# ESP-32-UNICLOCK-Z560M-V2.net
KiCad netlist of a schematic drawn in EAGLE
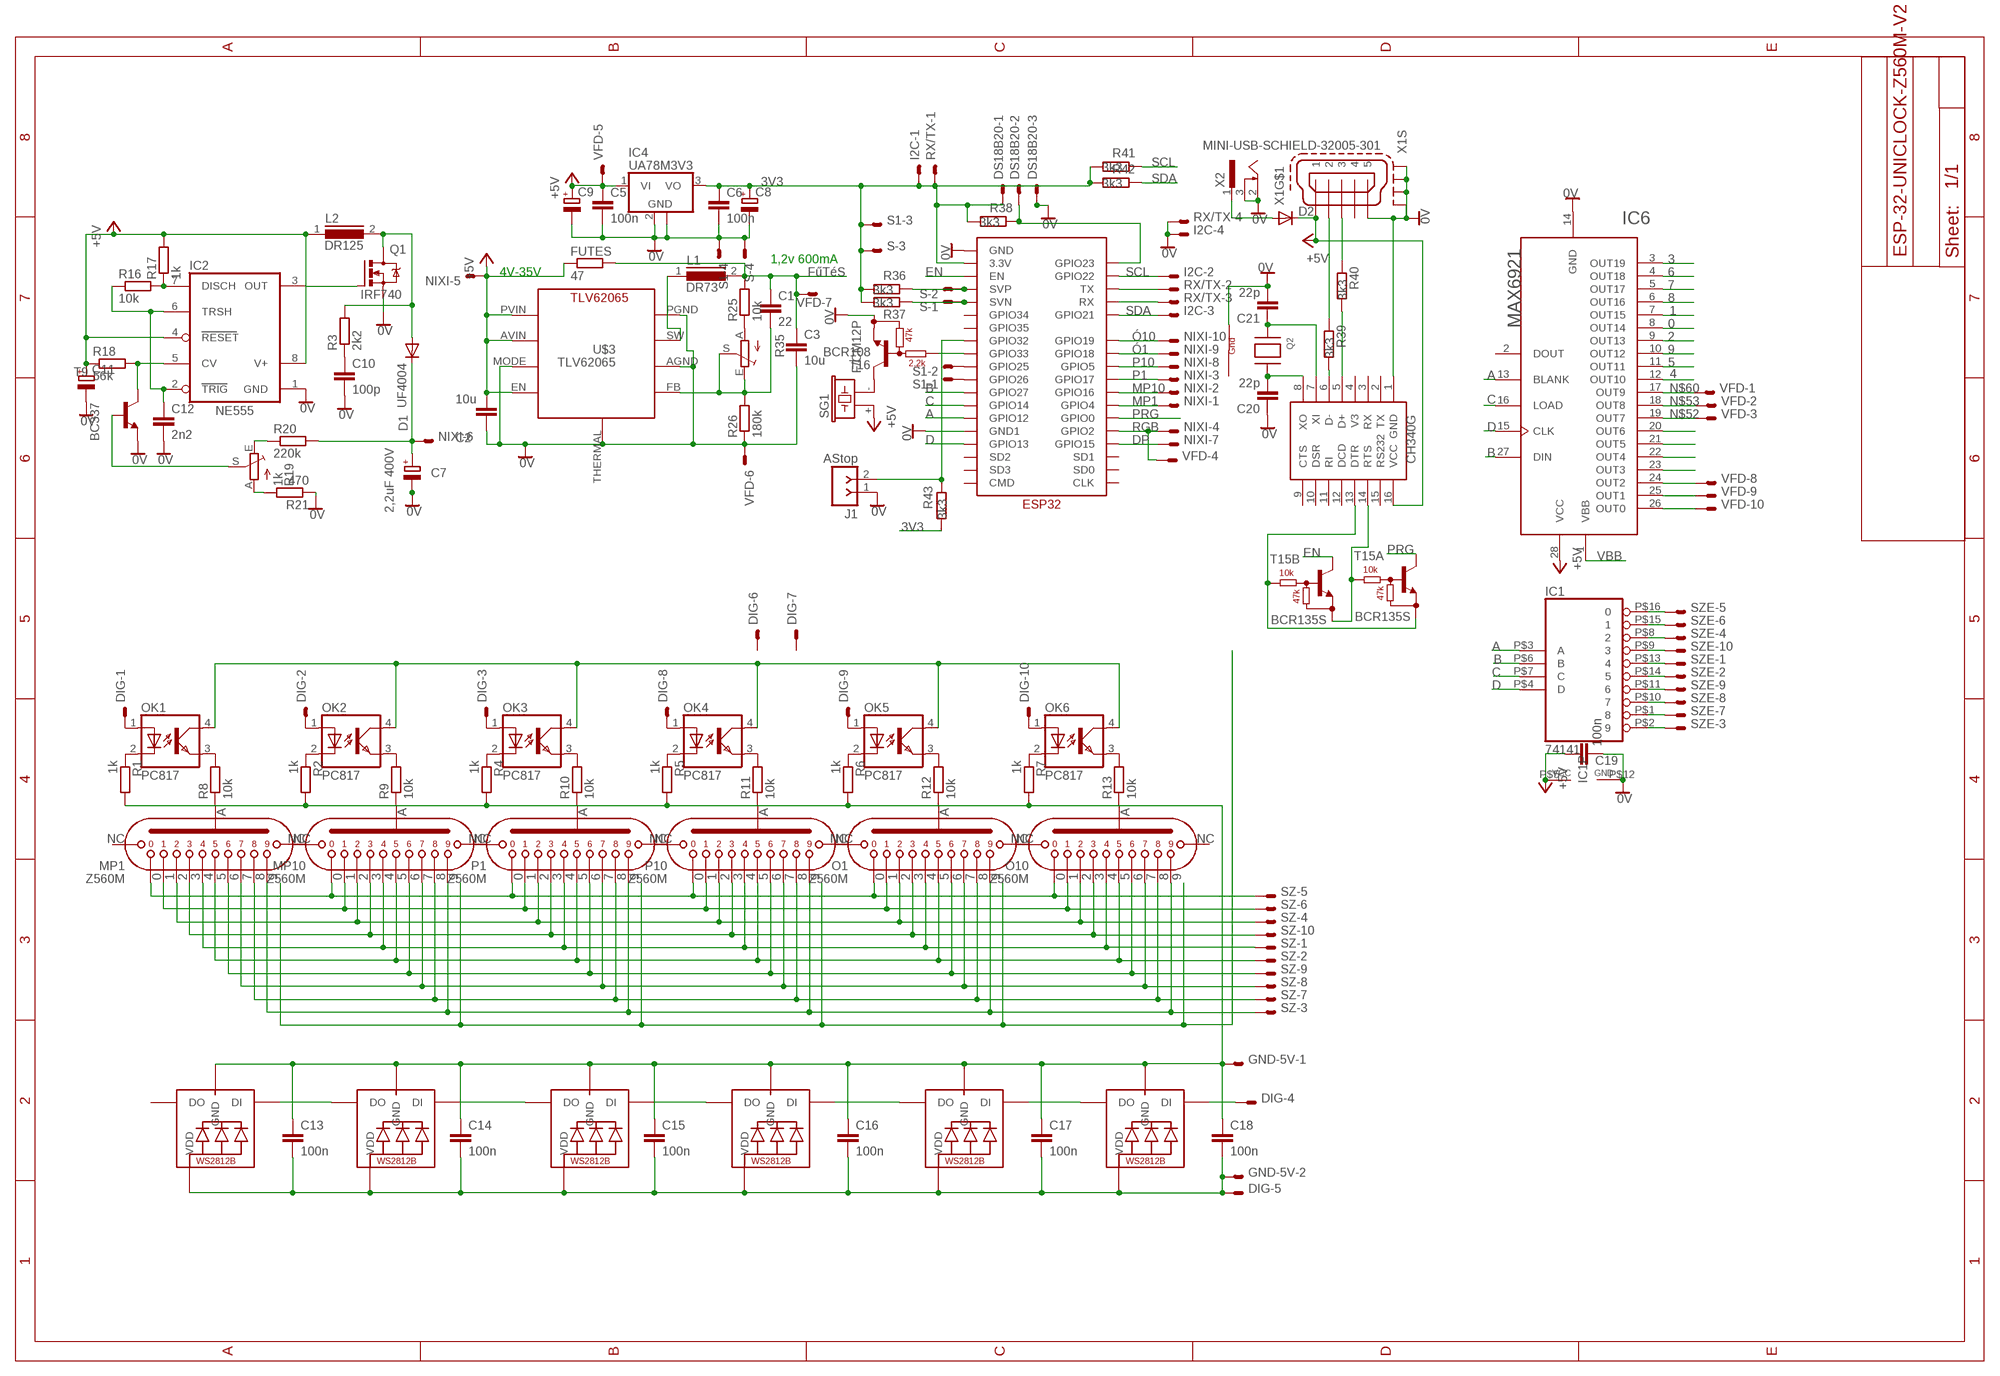
[diagram p0: schematic, sheet 1]

(export (version "E")
  (design (tool "Eeschema 10.0.6"))
  (components
    (comp (ref "C1")
      (value "22")
      (footprint "eagle-import:0603")
      (libsource (lib "eagle-import") (part "C0603"))
    )
    (comp (ref "C2")
      (value "10u")
      (footprint "eagle-import:1206")
      (libsource (lib "eagle-import") (part "C1206"))
    )
    (comp (ref "C3")
      (value "10u")
      (footprint "eagle-import:1206")
      (libsource (lib "eagle-import") (part "C1206"))
    )
    (comp (ref "C5")
      (value "100n")
      (footprint "eagle-import:0603")
      (libsource (lib "eagle-import") (part "C0603"))
    )
    (comp (ref "C6")
      (value "100n")
      (footprint "eagle-import:0603")
      (libsource (lib "eagle-import") (part "C0603"))
    )
    (comp (ref "C7")
      (value "2,2uF 400V")
      (footprint "eagle-import:E2,5-7")
      (libsource (lib "eagle-import") (part "CPOL-EUE2.5-7"))
    )
    (comp (ref "C8")
      (value "CPOL-EUE2.5-5")
      (footprint "eagle-import:E2,5-5")
      (libsource (lib "eagle-import") (part "CPOL-EUE2.5-5"))
    )
    (comp (ref "C9")
      (value "CPOL-EUE2.5-5")
      (footprint "eagle-import:E2,5-5")
      (libsource (lib "eagle-import") (part "CPOL-EUE2.5-5"))
    )
    (comp (ref "C10")
      (value "100p")
      (footprint "eagle-import:C050-024X044")
      (libsource (lib "eagle-import") (part "C-EU050-024X044"))
    )
    (comp (ref "C11")
      (value "CPOL-EUE2.5-7")
      (footprint "eagle-import:E2,5-7")
      (libsource (lib "eagle-import") (part "CPOL-EUE2.5-7"))
    )
    (comp (ref "C12")
      (value "2n2")
      (footprint "eagle-import:C0603")
      (libsource (lib "eagle-import") (part "C-EUC0603"))
    )
    (comp (ref "C13")
      (value "100n")
      (footprint "eagle-import:C0603")
      (libsource (lib "eagle-import") (part "C-EUC0603"))
    )
    (comp (ref "C14")
      (value "100n")
      (footprint "eagle-import:C0603")
      (libsource (lib "eagle-import") (part "C-EUC0603"))
    )
    (comp (ref "C15")
      (value "100n")
      (footprint "eagle-import:C0603")
      (libsource (lib "eagle-import") (part "C-EUC0603"))
    )
    (comp (ref "C16")
      (value "100n")
      (footprint "eagle-import:C0603")
      (libsource (lib "eagle-import") (part "C-EUC0603"))
    )
    (comp (ref "C17")
      (value "100n")
      (footprint "eagle-import:C0603")
      (libsource (lib "eagle-import") (part "C-EUC0603"))
    )
    (comp (ref "C18")
      (value "100n")
      (footprint "eagle-import:C0603")
      (libsource (lib "eagle-import") (part "C-EUC0603"))
    )
    (comp (ref "C19")
      (value "100n")
      (footprint "eagle-import:0603")
      (libsource (lib "eagle-import") (part "C0603"))
    )
    (comp (ref "C20")
      (value "22p")
      (footprint "eagle-import:0603")
      (libsource (lib "eagle-import") (part "C0603"))
    )
    (comp (ref "C21")
      (value "22p")
      (footprint "eagle-import:0603")
      (libsource (lib "eagle-import") (part "C0603"))
    )
    (comp (ref "D1")
      (value "UF4004")
      (footprint "eagle-import:DO35-10")
      (libsource (lib "eagle-import") (part "BA221"))
    )
    (comp (ref "D2")
      (value "DIODE-SOD123")
      (footprint "eagle-import:SOD123")
      (libsource (lib "eagle-import") (part "DIODE-SOD123"))
    )
    (comp (ref "DIG")
      (value "DIG")
      (footprint "eagle-import:PAD10")
      (libsource (lib "eagle-import") (part "PAD10"))
    )
    (comp (ref "DS18B20")
      (value "PAD3")
      (footprint "eagle-import:PAD3")
      (libsource (lib "eagle-import") (part "PAD3"))
    )
    (comp (ref "FUTES")
      (value "47")
      (footprint "eagle-import:0207_10")
      (libsource (lib "eagle-import") (part "R-EU_0207/10"))
    )
    (comp (ref "GND-5V")
      (value "PAD2")
      (footprint "eagle-import:PAD2")
      (libsource (lib "eagle-import") (part "PAD2"))
    )
    (comp (ref "I2C")
      (value "PAD4")
      (footprint "eagle-import:PAD4")
      (libsource (lib "eagle-import") (part "PAD4"))
    )
    (comp (ref "IC1")
      (value "74141")
      (footprint "eagle-import:DIL16SMD")
      (libsource (lib "eagle-import") (part "74141"))
    )
    (comp (ref "IC2")
      (value "NE555")
      (footprint "eagle-import:DIL08")
      (fields (field (name "MF") "MAXIM") (field (name "MPN") "ICM7555IPA+"))
      (libsource (lib "eagle-import") (part "ICM7555"))
    )
    (comp (ref "IC4")
      (value "UA78M3V3")
      (footprint "eagle-import:SOT223")
      (libsource (lib "eagle-import") (part "UA78MDCY05"))
    )
    (comp (ref "IC6")
      (value "MAX6921")
      (footprint "eagle-import:SO-28W")
      (libsource (lib "eagle-import") (part "MAX6921SOIC28W"))
    )
    (comp (ref "J1")
      (value "AStop")
      (footprint "eagle-import:SIP-100-02-32")
      (libsource (lib "eagle-import") (part "F-1X02-SIP-100-32"))
    )
    (comp (ref "L1")
      (value "DR73")
      (footprint "eagle-import:DR73")
      (libsource (lib "eagle-import") (part "DR73"))
    )
    (comp (ref "L2")
      (value "DR125")
      (footprint "eagle-import:DR125")
      (libsource (lib "eagle-import") (part "DR125"))
    )
    (comp (ref "LED1")
      (value "WS2812B_5050N")
      (footprint "eagle-import:WS2812B-NARROW")
      (libsource (lib "eagle-import") (part "WS2812B_5050N"))
    )
    (comp (ref "LED2")
      (value "WS2812B_5050N")
      (footprint "eagle-import:WS2812B-NARROW")
      (libsource (lib "eagle-import") (part "WS2812B_5050N"))
    )
    (comp (ref "LED3")
      (value "WS2812B_5050N")
      (footprint "eagle-import:WS2812B-NARROW")
      (libsource (lib "eagle-import") (part "WS2812B_5050N"))
    )
    (comp (ref "LED4")
      (value "WS2812B_5050N")
      (footprint "eagle-import:WS2812B-NARROW")
      (libsource (lib "eagle-import") (part "WS2812B_5050N"))
    )
    (comp (ref "LED5")
      (value "WS2812B_5050N")
      (footprint "eagle-import:WS2812B-NARROW")
      (libsource (lib "eagle-import") (part "WS2812B_5050N"))
    )
    (comp (ref "LED6")
      (value "WS2812B_5050N")
      (footprint "eagle-import:WS2812B-NARROW")
      (libsource (lib "eagle-import") (part "WS2812B_5050N"))
    )
    (comp (ref "MP1")
      (value "Z560M")
      (footprint "eagle-import:Z560M")
      (libsource (lib "eagle-import") (part "Z560M"))
    )
    (comp (ref "MP10")
      (value "Z560M")
      (footprint "eagle-import:Z560M")
      (libsource (lib "eagle-import") (part "Z560M"))
    )
    (comp (ref "NIXI")
      (value "PAD10")
      (footprint "eagle-import:PAD10")
      (libsource (lib "eagle-import") (part "PAD10"))
    )
    (comp (ref "O1")
      (value "Z560M")
      (footprint "eagle-import:Z560M")
      (libsource (lib "eagle-import") (part "Z560M"))
    )
    (comp (ref "O10")
      (value "Z560M")
      (footprint "eagle-import:Z560M")
      (libsource (lib "eagle-import") (part "Z560M"))
    )
    (comp (ref "OK1")
      (value "PC817")
      (footprint "eagle-import:DIL04")
      (fields (field (name "MPN") "PC817X4J000F"))
      (libsource (lib "eagle-import") (part "PC817"))
    )
    (comp (ref "OK2")
      (value "PC817")
      (footprint "eagle-import:DIL04")
      (fields (field (name "MPN") "PC817X4J000F"))
      (libsource (lib "eagle-import") (part "PC817"))
    )
    (comp (ref "OK3")
      (value "PC817")
      (footprint "eagle-import:DIL04")
      (fields (field (name "MPN") "PC817X4J000F"))
      (libsource (lib "eagle-import") (part "PC817"))
    )
    (comp (ref "OK4")
      (value "PC817")
      (footprint "eagle-import:DIL04")
      (fields (field (name "MPN") "PC817X4J000F"))
      (libsource (lib "eagle-import") (part "PC817"))
    )
    (comp (ref "OK5")
      (value "PC817")
      (footprint "eagle-import:DIL04")
      (fields (field (name "MPN") "PC817X4J000F"))
      (libsource (lib "eagle-import") (part "PC817"))
    )
    (comp (ref "OK6")
      (value "PC817")
      (footprint "eagle-import:DIL04")
      (fields (field (name "MPN") "PC817X4J000F"))
      (libsource (lib "eagle-import") (part "PC817"))
    )
    (comp (ref "P1")
      (value "Z560M")
      (footprint "eagle-import:Z560M")
      (libsource (lib "eagle-import") (part "Z560M"))
    )
    (comp (ref "P10")
      (value "Z560M")
      (footprint "eagle-import:Z560M")
      (libsource (lib "eagle-import") (part "Z560M"))
    )
    (comp (ref "Q1")
      (value "IRF740")
      (footprint "eagle-import:TO220BV")
      (libsource (lib "eagle-import") (part "IRF740"))
    )
    (comp (ref "Q2")
      (value "XTAL-4-3225")
      (footprint "eagle-import:NX3225")
      (libsource (lib "eagle-import") (part "XTAL-4-3225"))
    )
    (comp (ref "R1")
      (value "1k")
      (footprint "eagle-import:0603")
      (libsource (lib "eagle-import") (part "R0603"))
    )
    (comp (ref "R2")
      (value "1k")
      (footprint "eagle-import:0603")
      (libsource (lib "eagle-import") (part "R0603"))
    )
    (comp (ref "R3")
      (value "2k2")
      (footprint "eagle-import:0204_7")
      (libsource (lib "eagle-import") (part "R-EU_0204/7"))
    )
    (comp (ref "R4")
      (value "1k")
      (footprint "eagle-import:0603")
      (libsource (lib "eagle-import") (part "R0603"))
    )
    (comp (ref "R5")
      (value "1k")
      (footprint "eagle-import:0603")
      (libsource (lib "eagle-import") (part "R0603"))
    )
    (comp (ref "R6")
      (value "1k")
      (footprint "eagle-import:0603")
      (libsource (lib "eagle-import") (part "R0603"))
    )
    (comp (ref "R7")
      (value "1k")
      (footprint "eagle-import:0603")
      (libsource (lib "eagle-import") (part "R0603"))
    )
    (comp (ref "R8")
      (value "10k")
      (footprint "eagle-import:0207_10")
      (libsource (lib "eagle-import") (part "R-EU_0207/10"))
    )
    (comp (ref "R9")
      (value "10k")
      (footprint "eagle-import:0207_10")
      (libsource (lib "eagle-import") (part "R-EU_0207/10"))
    )
    (comp (ref "R10")
      (value "10k")
      (footprint "eagle-import:0207_10")
      (libsource (lib "eagle-import") (part "R-EU_0207/10"))
    )
    (comp (ref "R11")
      (value "10k")
      (footprint "eagle-import:0207_10")
      (libsource (lib "eagle-import") (part "R-EU_0207/10"))
    )
    (comp (ref "R12")
      (value "10k")
      (footprint "eagle-import:0207_10")
      (libsource (lib "eagle-import") (part "R-EU_0207/10"))
    )
    (comp (ref "R13")
      (value "10k")
      (footprint "eagle-import:0207_10")
      (libsource (lib "eagle-import") (part "R-EU_0207/10"))
    )
    (comp (ref "R16")
      (value "10k")
      (footprint "eagle-import:R0603")
      (libsource (lib "eagle-import") (part "R-EU_R0603"))
    )
    (comp (ref "R17")
      (value "1k")
      (footprint "eagle-import:R0603")
      (libsource (lib "eagle-import") (part "R-EU_R0603"))
    )
    (comp (ref "R18")
      (value "56k")
      (footprint "eagle-import:R0603")
      (libsource (lib "eagle-import") (part "R-EU_R0603"))
    )
    (comp (ref "R19")
      (value "1k")
      (footprint "eagle-import:CA6H")
      (libsource (lib "eagle-import") (part "TRIM_EU-CA6H"))
    )
    (comp (ref "R20")
      (value "220k")
      (footprint "eagle-import:0204_7")
      (libsource (lib "eagle-import") (part "R-EU_0204/7"))
    )
    (comp (ref "R21")
      (value "470")
      (footprint "eagle-import:0204_7")
      (libsource (lib "eagle-import") (part "R-EU_0204/7"))
    )
    (comp (ref "R25")
      (value "10k")
      (footprint "eagle-import:0603")
      (libsource (lib "eagle-import") (part "R0603"))
    )
    (comp (ref "R26")
      (value "180k")
      (footprint "eagle-import:0603")
      (libsource (lib "eagle-import") (part "R0603"))
    )
    (comp (ref "R35")
      (value "TRIM_EU-B25P")
      (footprint "eagle-import:B25P")
      (libsource (lib "eagle-import") (part "TRIM_EU-B25P"))
    )
    (comp (ref "R36")
      (value "3k3")
      (footprint "eagle-import:0603")
      (libsource (lib "eagle-import") (part "R0603"))
    )
    (comp (ref "R37")
      (value "3k3")
      (footprint "eagle-import:0603")
      (libsource (lib "eagle-import") (part "R0603"))
    )
    (comp (ref "R38")
      (value "3k3")
      (footprint "eagle-import:0603")
      (libsource (lib "eagle-import") (part "R0603"))
    )
    (comp (ref "R39")
      (value "3k3")
      (footprint "eagle-import:0603")
      (libsource (lib "eagle-import") (part "R0603"))
    )
    (comp (ref "R40")
      (value "3k3")
      (footprint "eagle-import:0603")
      (libsource (lib "eagle-import") (part "R0603"))
    )
    (comp (ref "R41")
      (value "3k3")
      (footprint "eagle-import:0603")
      (libsource (lib "eagle-import") (part "R0603"))
    )
    (comp (ref "R42")
      (value "3k3")
      (footprint "eagle-import:0603")
      (libsource (lib "eagle-import") (part "R0603"))
    )
    (comp (ref "R43")
      (value "3k3")
      (footprint "eagle-import:0603")
      (libsource (lib "eagle-import") (part "R0603"))
    )
    (comp (ref "RX/TX")
      (value "PAD4")
      (footprint "eagle-import:PAD4")
      (libsource (lib "eagle-import") (part "PAD4"))
    )
    (comp (ref "S")
      (value "PAD4")
      (footprint "eagle-import:PAD4")
      (libsource (lib "eagle-import") (part "PAD4"))
    )
    (comp (ref "S1")
      (value "PAD4")
      (footprint "eagle-import:PAD4")
      (libsource (lib "eagle-import") (part "PAD4"))
    )
    (comp (ref "SG1")
      (value "F/CM12P")
      (footprint "eagle-import:F_CM12P")
      (libsource (lib "eagle-import") (part "F/CM12P"))
    )
    (comp (ref "SZ")
      (value "PAD10")
      (footprint "eagle-import:PAD10")
      (libsource (lib "eagle-import") (part "PAD10"))
    )
    (comp (ref "SZE")
      (value "PAD10")
      (footprint "eagle-import:PAD10")
      (libsource (lib "eagle-import") (part "PAD10"))
    )
    (comp (ref "T9")
      (value "BC337")
      (footprint "eagle-import:TO92-CBE")
      (libsource (lib "eagle-import") (part "-NPN-TO92-CBEBC237"))
    )
    (comp (ref "T15")
      (value "BCR135S")
      (footprint "eagle-import:SOT363_INFINEON")
      (libsource (lib "eagle-import") (part "BCR135S"))
    )
    (comp (ref "T16")
      (value "BCR108")
      (footprint "eagle-import:SOT23-BEC")
      (libsource (lib "eagle-import") (part "BCR108"))
    )
    (comp (ref "U$1")
      (value "CH340G")
      (footprint "eagle-import:SOIC16")
      (libsource (lib "eagle-import") (part "CH340G"))
    )
    (comp (ref "U$2")
      (value "ESP32-2X18")
      (footprint "eagle-import:ESP322X18")
      (libsource (lib "eagle-import") (part "ESP32-2X18"))
    )
    (comp (ref "U$3")
      (value "TLV62065")
      (footprint "eagle-import:TLV62065")
      (libsource (lib "eagle-import") (part "TLV62065"))
    )
    (comp (ref "VFD")
      (value "PAD10")
      (footprint "eagle-import:PAD10")
      (libsource (lib "eagle-import") (part "PAD10"))
    )
    (comp (ref "X1")
      (value "MINI-USB-SCHIELD-32005-301")
      (footprint "eagle-import:32005-301")
      (libsource (lib "eagle-import") (part "MINI-USB-SCHIELD-32005-301"))
    )
    (comp (ref "X2")
      (value "733989-5")
      (footprint "eagle-import:733989-5")
      (libsource (lib "eagle-import") (part "73398?9-5"))
    )
  )
  (nets
    (net (code "1") (name "+5V") (class "Default")
      (node (ref "C11") (pin "+") (pinfunction "+_+") (pintype "passive"))
      (node (ref "C19") (pin "1") (pinfunction "1_1") (pintype "passive"))
      (node (ref "C2") (pin "1") (pinfunction "1_1") (pintype "passive"))
      (node (ref "C5") (pin "1") (pinfunction "1_1") (pintype "passive"))
      (node (ref "C9") (pin "+") (pinfunction "+_+") (pintype "passive"))
      (node (ref "D2") (pin "C") (pinfunction "C_C") (pintype "passive"))
      (node (ref "FUTES") (pin "1") (pinfunction "1_1") (pintype "passive"))
      (node (ref "IC1") (pin "P$5") (pinfunction "VCC_P$5") (pintype "power_in"))
      (node (ref "IC2") (pin "4") (pinfunction "RESET_4") (pintype "input"))
      (node (ref "IC2") (pin "8") (pinfunction "V+_8") (pintype "power_in"))
      (node (ref "IC4") (pin "1") (pinfunction "VI_1") (pintype "input"))
      (node (ref "IC6") (pin "28") (pinfunction "VCC_28") (pintype "power_in"))
      (node (ref "L2") (pin "1") (pinfunction "1_1") (pintype "passive"))
      (node (ref "NIXI") (pin "P$5") (pinfunction "S_P$5") (pintype "passive"))
      (node (ref "R17") (pin "2") (pinfunction "2_2") (pintype "passive"))
      (node (ref "R18") (pin "1") (pinfunction "1_1") (pintype "passive"))
      (node (ref "SG1") (pin "+") (pinfunction "1_+") (pintype "passive"))
      (node (ref "U$1") (pin "16") (pinfunction "VCC_16") (pintype "bidirectional"))
      (node (ref "U$3") (pin "AVIN") (pinfunction "AVIN_AVIN") (pintype "bidirectional"))
      (node (ref "U$3") (pin "EN") (pinfunction "EN_EN") (pintype "bidirectional"))
      (node (ref "U$3") (pin "PVIN") (pinfunction "PVIN_PVIN") (pintype "bidirectional"))
      (node (ref "VFD") (pin "P$5") (pinfunction "S_P$5") (pintype "passive"))
      (node (ref "X1") (pin "1") (pinfunction "1_1") (pintype "passive"))
    )
    (net (code "2") (name "/0") (class "Default")
      (node (ref "IC1") (pin "P$16") (pinfunction "0_P$16") (pintype "open_collector"))
      (node (ref "IC6") (pin "8") (pinfunction "OUT14_8") (pintype "output"))
      (node (ref "SZE") (pin "P$5") (pinfunction "S_P$5") (pintype "passive"))
    )
    (net (code "3") (name "/1") (class "Default")
      (node (ref "IC1") (pin "P$15") (pinfunction "1_P$15") (pintype "open_collector"))
      (node (ref "IC6") (pin "7") (pinfunction "OUT15_7") (pintype "output"))
      (node (ref "SZE") (pin "P$6") (pinfunction "S_P$6") (pintype "passive"))
    )
    (net (code "4") (name "/2") (class "Default")
      (node (ref "IC1") (pin "P$8") (pinfunction "2_P$8") (pintype "open_collector"))
      (node (ref "IC6") (pin "9") (pinfunction "OUT13_9") (pintype "output"))
      (node (ref "SZE") (pin "P$4") (pinfunction "S_P$4") (pintype "passive"))
    )
    (net (code "5") (name "/3") (class "Default")
      (node (ref "IC1") (pin "P$9") (pinfunction "3_P$9") (pintype "open_collector"))
      (node (ref "IC6") (pin "3") (pinfunction "OUT19_3") (pintype "output"))
      (node (ref "SZE") (pin "P$10") (pinfunction "S_P$10") (pintype "passive"))
    )
    (net (code "6") (name "/3V3") (class "Default")
      (node (ref "C6") (pin "1") (pinfunction "1_1") (pintype "passive"))
      (node (ref "C8") (pin "+") (pinfunction "+_+") (pintype "passive"))
      (node (ref "DS18B20") (pin "P$1") (pinfunction "S_P$1") (pintype "passive"))
      (node (ref "I2C") (pin "P$1") (pinfunction "S_P$1") (pintype "passive"))
      (node (ref "IC4") (pin "3") (pinfunction "VO_3") (pintype "passive"))
      (node (ref "R36") (pin "2") (pinfunction "2_2") (pintype "passive"))
      (node (ref "R37") (pin "2") (pinfunction "2_2") (pintype "passive"))
      (node (ref "R38") (pin "2") (pinfunction "2_2") (pintype "passive"))
      (node (ref "R41") (pin "2") (pinfunction "2_2") (pintype "passive"))
      (node (ref "R42") (pin "2") (pinfunction "2_2") (pintype "passive"))
      (node (ref "R43") (pin "2") (pinfunction "2_2") (pintype "passive"))
      (node (ref "RX/TX") (pin "P$1") (pinfunction "S_P$1") (pintype "passive"))
      (node (ref "S") (pin "P$3") (pinfunction "S_P$3") (pintype "passive"))
      (node (ref "S1") (pin "P$3") (pinfunction "S_P$3") (pintype "passive"))
      (node (ref "U$2") (pin "P$20") (pinfunction "3.3V_P$20") (pintype "bidirectional"))
    )
    (net (code "7") (name "/4") (class "Default")
      (node (ref "IC1") (pin "P$13") (pinfunction "4_P$13") (pintype "open_collector"))
      (node (ref "IC6") (pin "12") (pinfunction "OUT10_12") (pintype "output"))
      (node (ref "SZE") (pin "P$1") (pinfunction "S_P$1") (pintype "passive"))
    )
    (net (code "8") (name "/5") (class "Default")
      (node (ref "IC1") (pin "P$14") (pinfunction "5_P$14") (pintype "open_collector"))
      (node (ref "IC6") (pin "11") (pinfunction "OUT11_11") (pintype "output"))
      (node (ref "SZE") (pin "P$2") (pinfunction "S_P$2") (pintype "passive"))
    )
    (net (code "9") (name "/6") (class "Default")
      (node (ref "IC1") (pin "P$11") (pinfunction "6_P$11") (pintype "open_collector"))
      (node (ref "IC6") (pin "4") (pinfunction "OUT18_4") (pintype "output"))
      (node (ref "SZE") (pin "P$9") (pinfunction "S_P$9") (pintype "passive"))
    )
    (net (code "10") (name "/7") (class "Default")
      (node (ref "IC1") (pin "P$10") (pinfunction "7_P$10") (pintype "open_collector"))
      (node (ref "IC6") (pin "5") (pinfunction "OUT17_5") (pintype "output"))
      (node (ref "SZE") (pin "P$8") (pinfunction "S_P$8") (pintype "passive"))
    )
    (net (code "11") (name "/8") (class "Default")
      (node (ref "IC1") (pin "P$1") (pinfunction "8_P$1") (pintype "open_collector"))
      (node (ref "IC6") (pin "6") (pinfunction "OUT16_6") (pintype "output"))
      (node (ref "SZE") (pin "P$7") (pinfunction "S_P$7") (pintype "passive"))
    )
    (net (code "12") (name "/9") (class "Default")
      (node (ref "IC1") (pin "P$2") (pinfunction "9_P$2") (pintype "open_collector"))
      (node (ref "IC6") (pin "10") (pinfunction "OUT12_10") (pintype "output"))
      (node (ref "SZE") (pin "P$3") (pinfunction "S_P$3") (pintype "passive"))
    )
    (net (code "13") (name "/A") (class "Default")
      (node (ref "IC1") (pin "P$3") (pinfunction "A_P$3") (pintype "input"))
      (node (ref "IC6") (pin "13") (pinfunction "BLANK_13") (pintype "input"))
      (node (ref "U$2") (pin "P$12") (pinfunction "GPIO12_P$12") (pintype "bidirectional"))
    )
    (net (code "14") (name "/B") (class "Default")
      (node (ref "IC1") (pin "P$6") (pinfunction "B_P$6") (pintype "input"))
      (node (ref "IC6") (pin "27") (pinfunction "DIN_27") (pintype "input"))
      (node (ref "U$2") (pin "P$10") (pinfunction "GPIO27_P$10") (pintype "bidirectional"))
    )
    (net (code "15") (name "/C") (class "Default")
      (node (ref "IC1") (pin "P$7") (pinfunction "C_P$7") (pintype "input"))
      (node (ref "IC6") (pin "16") (pinfunction "LOAD_16") (pintype "input"))
      (node (ref "U$2") (pin "P$9") (pinfunction "GPIO14_P$9") (pintype "bidirectional"))
    )
    (net (code "16") (name "/D") (class "Default")
      (node (ref "IC1") (pin "P$4") (pinfunction "D_P$4") (pintype "input"))
      (node (ref "IC6") (pin "15") (pinfunction "CLK_15") (pintype "input"))
      (node (ref "U$2") (pin "P$11") (pinfunction "GPIO13_P$11") (pintype "bidirectional"))
    )
    (net (code "17") (name "/DP") (class "Default")
      (node (ref "NIXI") (pin "P$7") (pinfunction "S_P$7") (pintype "passive"))
      (node (ref "U$2") (pin "P$35") (pinfunction "GPIO15_P$35") (pintype "bidirectional"))
    )
    (net (code "18") (name "/EN") (class "Default")
      (node (ref "T15") (pin "3") (pinfunction "C_3") (pintype "passive"))
      (node (ref "U$2") (pin "P$21") (pinfunction "EN_P$21") (pintype "bidirectional"))
    )
    (net (code "19") (name "/FűTéS") (class "Default")
      (node (ref "C1") (pin "1") (pinfunction "1_1") (pintype "passive"))
      (node (ref "C3") (pin "1") (pinfunction "1_1") (pintype "passive"))
      (node (ref "FUTES") (pin "2") (pinfunction "2_2") (pintype "passive"))
      (node (ref "L1") (pin "2") (pinfunction "2_2") (pintype "passive"))
      (node (ref "R25") (pin "2") (pinfunction "2_2") (pintype "passive"))
      (node (ref "VFD") (pin "P$7") (pinfunction "S_P$7") (pintype "passive"))
    )
    (net (code "20") (name "/G2") (class "Default")
      (node (ref "Q2") (pin "2") (pinfunction "G2_2") (pintype "power_in"))
    )
    (net (code "21") (name "/MP1") (class "Default")
      (node (ref "NIXI") (pin "P$1") (pinfunction "S_P$1") (pintype "passive"))
      (node (ref "U$2") (pin "P$34") (pinfunction "GPIO4_P$34") (pintype "bidirectional"))
    )
    (net (code "22") (name "/MP10") (class "Default")
      (node (ref "NIXI") (pin "P$2") (pinfunction "S_P$2") (pintype "passive"))
      (node (ref "U$2") (pin "P$31") (pinfunction "GPIO16_P$31") (pintype "bidirectional"))
    )
    (net (code "23") (name "/N$52") (class "Default")
      (node (ref "IC6") (pin "19") (pinfunction "OUT7_19") (pintype "output"))
      (node (ref "VFD") (pin "P$3") (pinfunction "S_P$3") (pintype "passive"))
    )
    (net (code "24") (name "/N$53") (class "Default")
      (node (ref "IC6") (pin "18") (pinfunction "OUT8_18") (pintype "output"))
      (node (ref "VFD") (pin "P$2") (pinfunction "S_P$2") (pintype "passive"))
    )
    (net (code "25") (name "/N$60") (class "Default")
      (node (ref "IC6") (pin "17") (pinfunction "OUT9_17") (pintype "output"))
      (node (ref "VFD") (pin "P$1") (pinfunction "S_P$1") (pintype "passive"))
    )
    (net (code "26") (name "/P1") (class "Default")
      (node (ref "NIXI") (pin "P$3") (pinfunction "S_P$3") (pintype "passive"))
      (node (ref "U$2") (pin "P$32") (pinfunction "GPIO17_P$32") (pintype "bidirectional"))
    )
    (net (code "27") (name "/P10") (class "Default")
      (node (ref "NIXI") (pin "P$8") (pinfunction "S_P$8") (pintype "passive"))
      (node (ref "U$2") (pin "P$29") (pinfunction "GPIO5_P$29") (pintype "bidirectional"))
    )
    (net (code "28") (name "/PRG") (class "Default")
      (node (ref "T15") (pin "6") (pinfunction "C_6") (pintype "passive"))
      (node (ref "U$2") (pin "P$33") (pinfunction "GPIO0_P$33") (pintype "bidirectional"))
    )
    (net (code "29") (name "/RGB") (class "Default")
      (node (ref "NIXI") (pin "P$4") (pinfunction "S_P$4") (pintype "passive"))
      (node (ref "U$2") (pin "P$36") (pinfunction "GPIO2_P$36") (pintype "bidirectional"))
      (node (ref "VFD") (pin "P$4") (pinfunction "S_P$4") (pintype "passive"))
    )
    (net (code "30") (name "/SCL") (class "Default")
      (node (ref "I2C") (pin "P$2") (pinfunction "S_P$2") (pintype "passive"))
      (node (ref "R41") (pin "1") (pinfunction "1_1") (pintype "passive"))
      (node (ref "U$2") (pin "P$25") (pinfunction "GPIO22_P$25") (pintype "bidirectional"))
    )
    (net (code "31") (name "/SDA") (class "Default")
      (node (ref "I2C") (pin "P$3") (pinfunction "S_P$3") (pintype "passive"))
      (node (ref "R42") (pin "1") (pinfunction "1_1") (pintype "passive"))
      (node (ref "U$2") (pin "P$28") (pinfunction "GPIO21_P$28") (pintype "bidirectional"))
    )
    (net (code "32") (name "/VBB") (class "Default")
      (node (ref "C7") (pin "+") (pinfunction "+_+") (pintype "passive"))
      (node (ref "D1") (pin "C") (pinfunction "C_C") (pintype "passive"))
      (node (ref "IC6") (pin "1") (pinfunction "VBB_1") (pintype "power_in"))
      (node (ref "NIXI") (pin "P$6") (pinfunction "S_P$6") (pintype "passive"))
      (node (ref "R20") (pin "2") (pinfunction "2_2") (pintype "passive"))
    )
    (net (code "33") (name "/Ó1") (class "Default")
      (node (ref "NIXI") (pin "P$9") (pinfunction "S_P$9") (pintype "passive"))
      (node (ref "U$2") (pin "P$30") (pinfunction "GPIO18_P$30") (pintype "bidirectional"))
    )
    (net (code "34") (name "/Ó10") (class "Default")
      (node (ref "NIXI") (pin "P$10") (pinfunction "S_P$10") (pintype "passive"))
      (node (ref "U$2") (pin "P$27") (pinfunction "GPIO19_P$27") (pintype "bidirectional"))
    )
    (net (code "35") (name "0V") (class "Default")
      (node (ref "C10") (pin "2") (pinfunction "2_2") (pintype "passive"))
      (node (ref "C11") (pin "-") (pinfunction "-_-") (pintype "passive"))
      (node (ref "C12") (pin "2") (pinfunction "2_2") (pintype "passive"))
      (node (ref "C19") (pin "2") (pinfunction "2_2") (pintype "passive"))
      (node (ref "C2") (pin "2") (pinfunction "2_2") (pintype "passive"))
      (node (ref "C20") (pin "1") (pinfunction "1_1") (pintype "passive"))
      (node (ref "C21") (pin "2") (pinfunction "2_2") (pintype "passive"))
      (node (ref "C3") (pin "2") (pinfunction "2_2") (pintype "passive"))
      (node (ref "C5") (pin "2") (pinfunction "2_2") (pintype "passive"))
      (node (ref "C6") (pin "2") (pinfunction "2_2") (pintype "passive"))
      (node (ref "C7") (pin "-") (pinfunction "-_-") (pintype "passive"))
      (node (ref "C8") (pin "-") (pinfunction "-_-") (pintype "passive"))
      (node (ref "C9") (pin "-") (pinfunction "-_-") (pintype "passive"))
      (node (ref "DS18B20") (pin "P$3") (pinfunction "S_P$3") (pintype "passive"))
      (node (ref "I2C") (pin "P$4") (pinfunction "S_P$4") (pintype "passive"))
      (node (ref "IC1") (pin "P$12") (pinfunction "GND_P$12") (pintype "power_in"))
      (node (ref "IC2") (pin "1") (pinfunction "GND_1") (pintype "power_in"))
      (node (ref "IC4") (pin "2") (pinfunction "GND_2") (pintype "passive"))
      (node (ref "IC4") (pin "4") (pinfunction "GND_4") (pintype "passive"))
      (node (ref "IC6") (pin "14") (pinfunction "GND_14") (pintype "power_in"))
      (node (ref "J1") (pin "1") (pinfunction "1_1") (pintype "passive"))
      (node (ref "Q1") (pin "S") (pinfunction "S_S") (pintype "passive"))
      (node (ref "Q2") (pin "4") (pinfunction "G1_4") (pintype "power_in"))
      (node (ref "R21") (pin "1") (pinfunction "1_1") (pintype "passive"))
      (node (ref "R26") (pin "1") (pinfunction "1_1") (pintype "passive"))
      (node (ref "RX/TX") (pin "P$4") (pinfunction "S_P$4") (pintype "passive"))
      (node (ref "S") (pin "P$4") (pinfunction "S_P$4") (pintype "passive"))
      (node (ref "S1") (pin "P$4") (pinfunction "S_P$4") (pintype "passive"))
      (node (ref "T16") (pin "E") (pinfunction "E_E") (pintype "passive"))
      (node (ref "T9") (pin "E") (pinfunction "E_E") (pintype "passive"))
      (node (ref "U$1") (pin "1") (pinfunction "GND_1") (pintype "bidirectional"))
      (node (ref "U$2") (pin "P$19") (pinfunction "GND_P$19") (pintype "bidirectional"))
      (node (ref "U$2") (pin "P$26") (pinfunction "GND1_P$26") (pintype "bidirectional"))
      (node (ref "U$3") (pin "AGND") (pinfunction "AGND_AGND") (pintype "bidirectional"))
      (node (ref "U$3") (pin "MODE") (pinfunction "MODE_MODE") (pintype "bidirectional"))
      (node (ref "U$3") (pin "PGND") (pinfunction "PGND_PGND") (pintype "bidirectional"))
      (node (ref "U$3") (pin "THERMAL") (pinfunction "THERMAL_THERMAL") (pintype "bidirectional"))
      (node (ref "VFD") (pin "P$6") (pinfunction "S_P$6") (pintype "passive"))
      (node (ref "X1") (pin "5") (pinfunction "5_5") (pintype "passive"))
      (node (ref "X1") (pin "M1") (pinfunction "S1_M1") (pintype "passive"))
      (node (ref "X1") (pin "M2") (pinfunction "S2_M2") (pintype "passive"))
      (node (ref "X1") (pin "M3") (pinfunction "S3_M3") (pintype "passive"))
      (node (ref "X1") (pin "M4") (pinfunction "S4_M4") (pintype "passive"))
      (node (ref "X2") (pin "2") (pinfunction "2_2") (pintype "passive"))
      (node (ref "X2") (pin "3") (pinfunction "3_3") (pintype "passive"))
    )
    (net (code "36") (name "Net-(C1-Pad2)") (class "Default")
      (node (ref "C1") (pin "2") (pinfunction "2_2") (pintype "passive"))
      (node (ref "R26") (pin "2") (pinfunction "2_2") (pintype "passive"))
      (node (ref "R35") (pin "E") (pinfunction "E_E") (pintype "passive"))
      (node (ref "R35") (pin "S") (pinfunction "S_S") (pintype "passive"))
      (node (ref "U$3") (pin "FB") (pinfunction "FB_FB") (pintype "bidirectional"))
    )
    (net (code "37") (name "Net-(C10-Pad1)") (class "Default")
      (node (ref "C10") (pin "1") (pinfunction "1_1") (pintype "passive"))
      (node (ref "R3") (pin "1") (pinfunction "1_1") (pintype "passive"))
    )
    (net (code "38") (name "Net-(D1-PadA)") (class "Default")
      (node (ref "D1") (pin "A") (pinfunction "A_A") (pintype "passive"))
      (node (ref "L2") (pin "2") (pinfunction "2_2") (pintype "passive"))
      (node (ref "Q1") (pin "D") (pinfunction "D_D") (pintype "passive"))
      (node (ref "R3") (pin "2") (pinfunction "2_2") (pintype "passive"))
    )
    (net (code "39") (name "Net-(D2-PadA)") (class "Default")
      (node (ref "D2") (pin "A") (pinfunction "A_A") (pintype "passive"))
      (node (ref "X2") (pin "1") (pinfunction "1_1") (pintype "passive"))
    )
    (net (code "40") (name "Net-(DIGA-S)") (class "Default")
      (node (ref "DIG") (pin "P$1") (pinfunction "S_P$1") (pintype "passive"))
      (node (ref "OK1") (pin "1") (pinfunction "A_1") (pintype "passive"))
    )
    (net (code "41") (name "Net-(DIGB-S)") (class "Default")
      (node (ref "DIG") (pin "P$10") (pinfunction "S_P$10") (pintype "passive"))
      (node (ref "OK6") (pin "1") (pinfunction "A_1") (pintype "passive"))
    )
    (net (code "42") (name "Net-(DIGC-S)") (class "Default")
      (node (ref "DIG") (pin "P$2") (pinfunction "S_P$2") (pintype "passive"))
      (node (ref "OK2") (pin "1") (pinfunction "A_1") (pintype "passive"))
    )
    (net (code "43") (name "Net-(DIGD-S)") (class "Default")
      (node (ref "DIG") (pin "P$3") (pinfunction "S_P$3") (pintype "passive"))
      (node (ref "OK3") (pin "1") (pinfunction "A_1") (pintype "passive"))
    )
    (net (code "44") (name "Net-(DIGE-S)") (class "Default")
      (node (ref "DIG") (pin "P$4") (pinfunction "S_P$4") (pintype "passive"))
      (node (ref "LED1") (pin "4-DIN") (pinfunction "DI_4-DIN") (pintype "input"))
    )
    (net (code "45") (name "Net-(DIGF-S)") (class "Default")
      (node (ref "C13") (pin "2") (pinfunction "2_2") (pintype "passive"))
      (node (ref "C14") (pin "2") (pinfunction "2_2") (pintype "passive"))
      (node (ref "C15") (pin "2") (pinfunction "2_2") (pintype "passive"))
      (node (ref "C16") (pin "2") (pinfunction "2_2") (pintype "passive"))
      (node (ref "C17") (pin "2") (pinfunction "2_2") (pintype "passive"))
      (node (ref "C18") (pin "2") (pinfunction "2_2") (pintype "passive"))
      (node (ref "DIG") (pin "P$5") (pinfunction "S_P$5") (pintype "passive"))
      (node (ref "GND-5V") (pin "P$2") (pinfunction "S_P$2") (pintype "passive"))
      (node (ref "LED1") (pin "1-VDD") (pinfunction "VDD_1-VDD") (pintype "power_in"))
      (node (ref "LED2") (pin "1-VDD") (pinfunction "VDD_1-VDD") (pintype "power_in"))
      (node (ref "LED3") (pin "1-VDD") (pinfunction "VDD_1-VDD") (pintype "power_in"))
      (node (ref "LED4") (pin "1-VDD") (pinfunction "VDD_1-VDD") (pintype "power_in"))
      (node (ref "LED5") (pin "1-VDD") (pinfunction "VDD_1-VDD") (pintype "power_in"))
      (node (ref "LED6") (pin "1-VDD") (pinfunction "VDD_1-VDD") (pintype "power_in"))
    )
    (net (code "46") (name "Net-(DIGI-S)") (class "Default")
      (node (ref "DIG") (pin "P$8") (pinfunction "S_P$8") (pintype "passive"))
      (node (ref "OK4") (pin "1") (pinfunction "A_1") (pintype "passive"))
    )
    (net (code "47") (name "Net-(DIGJ-S)") (class "Default")
      (node (ref "DIG") (pin "P$9") (pinfunction "S_P$9") (pintype "passive"))
      (node (ref "OK5") (pin "1") (pinfunction "A_1") (pintype "passive"))
    )
    (net (code "48") (name "Net-(DS18B20B-S)") (class "Default")
      (node (ref "DS18B20") (pin "P$2") (pinfunction "S_P$2") (pintype "passive"))
      (node (ref "R38") (pin "1") (pinfunction "1_1") (pintype "passive"))
      (node (ref "U$2") (pin "P$23") (pinfunction "GPIO23_P$23") (pintype "bidirectional"))
    )
    (net (code "49") (name "Net-(GND-5VA-S)") (class "Default")
      (node (ref "C13") (pin "1") (pinfunction "1_1") (pintype "passive"))
      (node (ref "C14") (pin "1") (pinfunction "1_1") (pintype "passive"))
      (node (ref "C15") (pin "1") (pinfunction "1_1") (pintype "passive"))
      (node (ref "C16") (pin "1") (pinfunction "1_1") (pintype "passive"))
      (node (ref "C17") (pin "1") (pinfunction "1_1") (pintype "passive"))
      (node (ref "C18") (pin "1") (pinfunction "1_1") (pintype "passive"))
      (node (ref "GND-5V") (pin "P$1") (pinfunction "S_P$1") (pintype "passive"))
      (node (ref "LED1") (pin "3-GND") (pinfunction "GND_3-GND") (pintype "power_in"))
      (node (ref "LED2") (pin "3-GND") (pinfunction "GND_3-GND") (pintype "power_in"))
      (node (ref "LED3") (pin "3-GND") (pinfunction "GND_3-GND") (pintype "power_in"))
      (node (ref "LED4") (pin "3-GND") (pinfunction "GND_3-GND") (pintype "power_in"))
      (node (ref "LED5") (pin "3-GND") (pinfunction "GND_3-GND") (pintype "power_in"))
      (node (ref "LED6") (pin "3-GND") (pinfunction "GND_3-GND") (pintype "power_in"))
      (node (ref "R1") (pin "2") (pinfunction "2_2") (pintype "passive"))
      (node (ref "R2") (pin "2") (pinfunction "2_2") (pintype "passive"))
      (node (ref "R4") (pin "2") (pinfunction "2_2") (pintype "passive"))
      (node (ref "R5") (pin "2") (pinfunction "2_2") (pintype "passive"))
      (node (ref "R6") (pin "2") (pinfunction "2_2") (pintype "passive"))
      (node (ref "R7") (pin "2") (pinfunction "2_2") (pintype "passive"))
    )
    (net (code "50") (name "Net-(IC2-CV)") (class "Default")
      (node (ref "IC2") (pin "5") (pinfunction "CV_5") (pintype "passive"))
      (node (ref "R18") (pin "2") (pinfunction "2_2") (pintype "passive"))
      (node (ref "T9") (pin "C") (pinfunction "C_C") (pintype "passive"))
    )
    (net (code "51") (name "Net-(IC2-DISCH)") (class "Default")
      (node (ref "IC2") (pin "7") (pinfunction "DISCH_7") (pintype "input"))
      (node (ref "R16") (pin "2") (pinfunction "2_2") (pintype "passive"))
      (node (ref "R17") (pin "1") (pinfunction "1_1") (pintype "passive"))
    )
    (net (code "52") (name "Net-(IC2-OUT)") (class "Default")
      (node (ref "IC2") (pin "3") (pinfunction "OUT_3") (pintype "output"))
      (node (ref "Q1") (pin "G") (pinfunction "G_G") (pintype "passive"))
    )
    (net (code "53") (name "Net-(IC2-TRIG)") (class "Default")
      (node (ref "C12") (pin "1") (pinfunction "1_1") (pintype "passive"))
      (node (ref "IC2") (pin "2") (pinfunction "TRIG_2") (pintype "bidirectional"))
      (node (ref "IC2") (pin "6") (pinfunction "TRSH_6") (pintype "input"))
      (node (ref "R16") (pin "1") (pinfunction "1_1") (pintype "passive"))
    )
    (net (code "54") (name "Net-(IC6-OUT0)") (class "Default")
      (node (ref "IC6") (pin "26") (pinfunction "OUT0_26") (pintype "output"))
      (node (ref "VFD") (pin "P$10") (pinfunction "S_P$10") (pintype "passive"))
    )
    (net (code "55") (name "Net-(IC6-OUT1)") (class "Default")
      (node (ref "IC6") (pin "25") (pinfunction "OUT1_25") (pintype "output"))
      (node (ref "VFD") (pin "P$9") (pinfunction "S_P$9") (pintype "passive"))
    )
    (net (code "56") (name "Net-(IC6-OUT2)") (class "Default")
      (node (ref "IC6") (pin "24") (pinfunction "OUT2_24") (pintype "output"))
      (node (ref "VFD") (pin "P$8") (pinfunction "S_P$8") (pintype "passive"))
    )
    (net (code "57") (name "Net-(L1-Pad1)") (class "Default")
      (node (ref "L1") (pin "1") (pinfunction "1_1") (pintype "passive"))
      (node (ref "U$3") (pin "SW") (pinfunction "SW_SW") (pintype "bidirectional"))
    )
    (net (code "58") (name "Net-(LED1-DO)") (class "Default")
      (node (ref "LED1") (pin "2-DOUT") (pinfunction "DO_2-DOUT") (pintype "output"))
      (node (ref "LED2") (pin "4-DIN") (pinfunction "DI_4-DIN") (pintype "input"))
    )
    (net (code "59") (name "Net-(LED2-DO)") (class "Default")
      (node (ref "LED2") (pin "2-DOUT") (pinfunction "DO_2-DOUT") (pintype "output"))
      (node (ref "LED3") (pin "4-DIN") (pinfunction "DI_4-DIN") (pintype "input"))
    )
    (net (code "60") (name "Net-(LED3-DO)") (class "Default")
      (node (ref "LED3") (pin "2-DOUT") (pinfunction "DO_2-DOUT") (pintype "output"))
      (node (ref "LED4") (pin "4-DIN") (pinfunction "DI_4-DIN") (pintype "input"))
    )
    (net (code "61") (name "Net-(LED4-DO)") (class "Default")
      (node (ref "LED4") (pin "2-DOUT") (pinfunction "DO_2-DOUT") (pintype "output"))
      (node (ref "LED5") (pin "4-DIN") (pinfunction "DI_4-DIN") (pintype "input"))
    )
    (net (code "62") (name "Net-(LED5-DO)") (class "Default")
      (node (ref "LED5") (pin "2-DOUT") (pinfunction "DO_2-DOUT") (pintype "output"))
      (node (ref "LED6") (pin "4-DIN") (pinfunction "DI_4-DIN") (pintype "input"))
    )
    (net (code "63") (name "Net-(MP1-0)") (class "Default")
      (node (ref "MP1") (pin "P3") (pinfunction "0_P3") (pintype "bidirectional"))
      (node (ref "MP10") (pin "P3") (pinfunction "0_P3") (pintype "bidirectional"))
      (node (ref "O1") (pin "P3") (pinfunction "0_P3") (pintype "bidirectional"))
      (node (ref "O10") (pin "P3") (pinfunction "0_P3") (pintype "bidirectional"))
      (node (ref "P1") (pin "P3") (pinfunction "0_P3") (pintype "bidirectional"))
      (node (ref "P10") (pin "P3") (pinfunction "0_P3") (pintype "bidirectional"))
      (node (ref "SZ") (pin "P$5") (pinfunction "S_P$5") (pintype "passive"))
    )
    (net (code "64") (name "Net-(MP1-1)") (class "Default")
      (node (ref "MP1") (pin "P13") (pinfunction "1_P13") (pintype "bidirectional"))
      (node (ref "MP10") (pin "P13") (pinfunction "1_P13") (pintype "bidirectional"))
      (node (ref "O1") (pin "P13") (pinfunction "1_P13") (pintype "bidirectional"))
      (node (ref "O10") (pin "P13") (pinfunction "1_P13") (pintype "bidirectional"))
      (node (ref "P1") (pin "P13") (pinfunction "1_P13") (pintype "bidirectional"))
      (node (ref "P10") (pin "P13") (pinfunction "1_P13") (pintype "bidirectional"))
      (node (ref "SZ") (pin "P$6") (pinfunction "S_P$6") (pintype "passive"))
    )
    (net (code "65") (name "Net-(MP1-2)") (class "Default")
      (node (ref "MP1") (pin "P12") (pinfunction "2_P12") (pintype "bidirectional"))
      (node (ref "MP10") (pin "P12") (pinfunction "2_P12") (pintype "bidirectional"))
      (node (ref "O1") (pin "P12") (pinfunction "2_P12") (pintype "bidirectional"))
      (node (ref "O10") (pin "P12") (pinfunction "2_P12") (pintype "bidirectional"))
      (node (ref "P1") (pin "P12") (pinfunction "2_P12") (pintype "bidirectional"))
      (node (ref "P10") (pin "P12") (pinfunction "2_P12") (pintype "bidirectional"))
      (node (ref "SZ") (pin "P$4") (pinfunction "S_P$4") (pintype "passive"))
    )
    (net (code "66") (name "Net-(MP1-3)") (class "Default")
      (node (ref "MP1") (pin "P11") (pinfunction "3_P11") (pintype "bidirectional"))
      (node (ref "MP10") (pin "P11") (pinfunction "3_P11") (pintype "bidirectional"))
      (node (ref "O1") (pin "P11") (pinfunction "3_P11") (pintype "bidirectional"))
      (node (ref "O10") (pin "P11") (pinfunction "3_P11") (pintype "bidirectional"))
      (node (ref "P1") (pin "P11") (pinfunction "3_P11") (pintype "bidirectional"))
      (node (ref "P10") (pin "P11") (pinfunction "3_P11") (pintype "bidirectional"))
      (node (ref "SZ") (pin "P$10") (pinfunction "S_P$10") (pintype "passive"))
    )
    (net (code "67") (name "Net-(MP1-4)") (class "Default")
      (node (ref "MP1") (pin "P10") (pinfunction "4_P10") (pintype "bidirectional"))
      (node (ref "MP10") (pin "P10") (pinfunction "4_P10") (pintype "bidirectional"))
      (node (ref "O1") (pin "P10") (pinfunction "4_P10") (pintype "bidirectional"))
      (node (ref "O10") (pin "P10") (pinfunction "4_P10") (pintype "bidirectional"))
      (node (ref "P1") (pin "P10") (pinfunction "4_P10") (pintype "bidirectional"))
      (node (ref "P10") (pin "P10") (pinfunction "4_P10") (pintype "bidirectional"))
      (node (ref "SZ") (pin "P$1") (pinfunction "S_P$1") (pintype "passive"))
    )
    (net (code "68") (name "Net-(MP1-5)") (class "Default")
      (node (ref "MP1") (pin "P9") (pinfunction "5_P9") (pintype "bidirectional"))
      (node (ref "MP10") (pin "P9") (pinfunction "5_P9") (pintype "bidirectional"))
      (node (ref "O1") (pin "P9") (pinfunction "5_P9") (pintype "bidirectional"))
      (node (ref "O10") (pin "P9") (pinfunction "5_P9") (pintype "bidirectional"))
      (node (ref "P1") (pin "P9") (pinfunction "5_P9") (pintype "bidirectional"))
      (node (ref "P10") (pin "P9") (pinfunction "5_P9") (pintype "bidirectional"))
      (node (ref "SZ") (pin "P$2") (pinfunction "S_P$2") (pintype "passive"))
    )
    (net (code "69") (name "Net-(MP1-6)") (class "Default")
      (node (ref "MP1") (pin "P7") (pinfunction "6_P7") (pintype "bidirectional"))
      (node (ref "MP10") (pin "P7") (pinfunction "6_P7") (pintype "bidirectional"))
      (node (ref "O1") (pin "P7") (pinfunction "6_P7") (pintype "bidirectional"))
      (node (ref "O10") (pin "P7") (pinfunction "6_P7") (pintype "bidirectional"))
      (node (ref "P1") (pin "P7") (pinfunction "6_P7") (pintype "bidirectional"))
      (node (ref "P10") (pin "P7") (pinfunction "6_P7") (pintype "bidirectional"))
      (node (ref "SZ") (pin "P$9") (pinfunction "S_P$9") (pintype "passive"))
    )
    (net (code "70") (name "Net-(MP1-7)") (class "Default")
      (node (ref "MP1") (pin "P6") (pinfunction "7_P6") (pintype "bidirectional"))
      (node (ref "MP10") (pin "P6") (pinfunction "7_P6") (pintype "bidirectional"))
      (node (ref "O1") (pin "P6") (pinfunction "7_P6") (pintype "bidirectional"))
      (node (ref "O10") (pin "P6") (pinfunction "7_P6") (pintype "bidirectional"))
      (node (ref "P1") (pin "P6") (pinfunction "7_P6") (pintype "bidirectional"))
      (node (ref "P10") (pin "P6") (pinfunction "7_P6") (pintype "bidirectional"))
      (node (ref "SZ") (pin "P$8") (pinfunction "S_P$8") (pintype "passive"))
    )
    (net (code "71") (name "Net-(MP1-8)") (class "Default")
      (node (ref "MP1") (pin "P5") (pinfunction "8_P5") (pintype "bidirectional"))
      (node (ref "MP10") (pin "P5") (pinfunction "8_P5") (pintype "bidirectional"))
      (node (ref "O1") (pin "P5") (pinfunction "8_P5") (pintype "bidirectional"))
      (node (ref "O10") (pin "P5") (pinfunction "8_P5") (pintype "bidirectional"))
      (node (ref "P1") (pin "P5") (pinfunction "8_P5") (pintype "bidirectional"))
      (node (ref "P10") (pin "P5") (pinfunction "8_P5") (pintype "bidirectional"))
      (node (ref "SZ") (pin "P$7") (pinfunction "S_P$7") (pintype "passive"))
    )
    (net (code "72") (name "Net-(MP1-9)") (class "Default")
      (node (ref "MP1") (pin "P4") (pinfunction "9_P4") (pintype "bidirectional"))
      (node (ref "MP10") (pin "P4") (pinfunction "9_P4") (pintype "bidirectional"))
      (node (ref "O1") (pin "P4") (pinfunction "9_P4") (pintype "bidirectional"))
      (node (ref "O10") (pin "P4") (pinfunction "9_P4") (pintype "bidirectional"))
      (node (ref "P1") (pin "P4") (pinfunction "9_P4") (pintype "bidirectional"))
      (node (ref "P10") (pin "P4") (pinfunction "9_P4") (pintype "bidirectional"))
      (node (ref "SZ") (pin "P$3") (pinfunction "S_P$3") (pintype "passive"))
    )
    (net (code "73") (name "Net-(MP1-A)") (class "Default")
      (node (ref "MP1") (pin "P2") (pinfunction "A_P2") (pintype "bidirectional"))
      (node (ref "R8") (pin "1") (pinfunction "1_1") (pintype "passive"))
    )
    (net (code "74") (name "Net-(MP10-A)") (class "Default")
      (node (ref "MP10") (pin "P2") (pinfunction "A_P2") (pintype "bidirectional"))
      (node (ref "R9") (pin "1") (pinfunction "1_1") (pintype "passive"))
    )
    (net (code "75") (name "Net-(O1-A)") (class "Default")
      (node (ref "O1") (pin "P2") (pinfunction "A_P2") (pintype "bidirectional"))
      (node (ref "R12") (pin "1") (pinfunction "1_1") (pintype "passive"))
    )
    (net (code "76") (name "Net-(O10-A)") (class "Default")
      (node (ref "O10") (pin "P2") (pinfunction "A_P2") (pintype "bidirectional"))
      (node (ref "R13") (pin "1") (pinfunction "1_1") (pintype "passive"))
    )
    (net (code "77") (name "Net-(OK1-C)") (class "Default")
      (node (ref "OK1") (pin "2") (pinfunction "C_2") (pintype "passive"))
      (node (ref "R1") (pin "1") (pinfunction "1_1") (pintype "passive"))
    )
    (net (code "78") (name "Net-(OK1-COL)") (class "Default")
      (node (ref "OK1") (pin "4") (pinfunction "COL_4") (pintype "passive"))
      (node (ref "OK2") (pin "4") (pinfunction "COL_4") (pintype "passive"))
      (node (ref "OK3") (pin "4") (pinfunction "COL_4") (pintype "passive"))
      (node (ref "OK4") (pin "4") (pinfunction "COL_4") (pintype "passive"))
      (node (ref "OK5") (pin "4") (pinfunction "COL_4") (pintype "passive"))
      (node (ref "OK6") (pin "4") (pinfunction "COL_4") (pintype "passive"))
    )
    (net (code "79") (name "Net-(OK1-EMIT)") (class "Default")
      (node (ref "OK1") (pin "3") (pinfunction "EMIT_3") (pintype "passive"))
      (node (ref "R8") (pin "2") (pinfunction "2_2") (pintype "passive"))
    )
    (net (code "80") (name "Net-(OK2-C)") (class "Default")
      (node (ref "OK2") (pin "2") (pinfunction "C_2") (pintype "passive"))
      (node (ref "R2") (pin "1") (pinfunction "1_1") (pintype "passive"))
    )
    (net (code "81") (name "Net-(OK2-EMIT)") (class "Default")
      (node (ref "OK2") (pin "3") (pinfunction "EMIT_3") (pintype "passive"))
      (node (ref "R9") (pin "2") (pinfunction "2_2") (pintype "passive"))
    )
    (net (code "82") (name "Net-(OK3-C)") (class "Default")
      (node (ref "OK3") (pin "2") (pinfunction "C_2") (pintype "passive"))
      (node (ref "R4") (pin "1") (pinfunction "1_1") (pintype "passive"))
    )
    (net (code "83") (name "Net-(OK3-EMIT)") (class "Default")
      (node (ref "OK3") (pin "3") (pinfunction "EMIT_3") (pintype "passive"))
      (node (ref "R10") (pin "2") (pinfunction "2_2") (pintype "passive"))
    )
    (net (code "84") (name "Net-(OK4-C)") (class "Default")
      (node (ref "OK4") (pin "2") (pinfunction "C_2") (pintype "passive"))
      (node (ref "R5") (pin "1") (pinfunction "1_1") (pintype "passive"))
    )
    (net (code "85") (name "Net-(OK4-EMIT)") (class "Default")
      (node (ref "OK4") (pin "3") (pinfunction "EMIT_3") (pintype "passive"))
      (node (ref "R11") (pin "2") (pinfunction "2_2") (pintype "passive"))
    )
    (net (code "86") (name "Net-(OK5-C)") (class "Default")
      (node (ref "OK5") (pin "2") (pinfunction "C_2") (pintype "passive"))
      (node (ref "R6") (pin "1") (pinfunction "1_1") (pintype "passive"))
    )
    (net (code "87") (name "Net-(OK5-EMIT)") (class "Default")
      (node (ref "OK5") (pin "3") (pinfunction "EMIT_3") (pintype "passive"))
      (node (ref "R12") (pin "2") (pinfunction "2_2") (pintype "passive"))
    )
    (net (code "88") (name "Net-(OK6-C)") (class "Default")
      (node (ref "OK6") (pin "2") (pinfunction "C_2") (pintype "passive"))
      (node (ref "R7") (pin "1") (pinfunction "1_1") (pintype "passive"))
    )
    (net (code "89") (name "Net-(OK6-EMIT)") (class "Default")
      (node (ref "OK6") (pin "3") (pinfunction "EMIT_3") (pintype "passive"))
      (node (ref "R13") (pin "2") (pinfunction "2_2") (pintype "passive"))
    )
    (net (code "90") (name "Net-(P1-A)") (class "Default")
      (node (ref "P1") (pin "P2") (pinfunction "A_P2") (pintype "bidirectional"))
      (node (ref "R10") (pin "1") (pinfunction "1_1") (pintype "passive"))
    )
    (net (code "91") (name "Net-(P10-A)") (class "Default")
      (node (ref "P10") (pin "P2") (pinfunction "A_P2") (pintype "bidirectional"))
      (node (ref "R11") (pin "1") (pinfunction "1_1") (pintype "passive"))
    )
    (net (code "92") (name "Net-(Q2-X1)") (class "Default")
      (node (ref "C21") (pin "1") (pinfunction "1_1") (pintype "passive"))
      (node (ref "Q2") (pin "1") (pinfunction "X1_1") (pintype "bidirectional"))
      (node (ref "U$1") (pin "7") (pinfunction "XI_7") (pintype "bidirectional"))
    )
    (net (code "93") (name "Net-(Q2-X2)") (class "Default")
      (node (ref "C20") (pin "2") (pinfunction "2_2") (pintype "passive"))
      (node (ref "Q2") (pin "3") (pinfunction "X2_3") (pintype "bidirectional"))
      (node (ref "U$1") (pin "8") (pinfunction "XO_8") (pintype "bidirectional"))
    )
    (net (code "94") (name "Net-(R19-PadA)") (class "Default")
      (node (ref "R19") (pin "A") (pinfunction "A_A") (pintype "passive"))
      (node (ref "R21") (pin "2") (pinfunction "2_2") (pintype "passive"))
    )
    (net (code "95") (name "Net-(R19-PadE)") (class "Default")
      (node (ref "R19") (pin "E") (pinfunction "E_E") (pintype "passive"))
      (node (ref "R20") (pin "1") (pinfunction "1_1") (pintype "passive"))
    )
    (net (code "96") (name "Net-(R19-PadS)") (class "Default")
      (node (ref "R19") (pin "S") (pinfunction "S_S") (pintype "passive"))
      (node (ref "T9") (pin "B") (pinfunction "B_B") (pintype "passive"))
    )
    (net (code "97") (name "Net-(R25-Pad1)") (class "Default")
      (node (ref "R25") (pin "1") (pinfunction "1_1") (pintype "passive"))
      (node (ref "R35") (pin "A") (pinfunction "A_A") (pintype "passive"))
    )
    (net (code "98") (name "Net-(R39-Pad1)") (class "Default")
      (node (ref "R39") (pin "1") (pinfunction "1_1") (pintype "passive"))
      (node (ref "X1") (pin "2") (pinfunction "2_2") (pintype "passive"))
    )
    (net (code "99") (name "Net-(R40-Pad1)") (class "Default")
      (node (ref "R40") (pin "1") (pinfunction "1_1") (pintype "passive"))
      (node (ref "X1") (pin "3") (pinfunction "3_3") (pintype "passive"))
    )
    (net (code "100") (name "Net-(RX/TXB-S)") (class "Default")
      (node (ref "RX/TX") (pin "P$2") (pinfunction "S_P$2") (pintype "passive"))
      (node (ref "U$2") (pin "P$22") (pinfunction "TX_P$22") (pintype "bidirectional"))
    )
    (net (code "101") (name "Net-(RX/TXC-S)") (class "Default")
      (node (ref "RX/TX") (pin "P$3") (pinfunction "S_P$3") (pintype "passive"))
      (node (ref "U$2") (pin "P$24") (pinfunction "RX_P$24") (pintype "bidirectional"))
    )
    (net (code "102") (name "Net-(S1A-S)") (class "Default")
      (node (ref "S1") (pin "P$1") (pinfunction "S_P$1") (pintype "passive"))
      (node (ref "U$2") (pin "P$7") (pinfunction "GPIO26_P$7") (pintype "bidirectional"))
    )
    (net (code "103") (name "Net-(S1B-S)") (class "Default")
      (node (ref "S1") (pin "P$2") (pinfunction "S_P$2") (pintype "passive"))
      (node (ref "U$2") (pin "P$8") (pinfunction "GPIO25_P$8") (pintype "bidirectional"))
    )
    (net (code "104") (name "Net-(SA-S)") (class "Default")
      (node (ref "R37") (pin "1") (pinfunction "1_1") (pintype "passive"))
      (node (ref "S") (pin "P$1") (pinfunction "S_P$1") (pintype "passive"))
      (node (ref "U$2") (pin "P$1") (pinfunction "SVN_P$1") (pintype "bidirectional"))
    )
    (net (code "105") (name "Net-(SB-S)") (class "Default")
      (node (ref "R36") (pin "1") (pinfunction "1_1") (pintype "passive"))
      (node (ref "S") (pin "P$2") (pinfunction "S_P$2") (pintype "passive"))
      (node (ref "U$2") (pin "P$2") (pinfunction "SVP_P$2") (pintype "bidirectional"))
    )
    (net (code "106") (name "Net-(SG1-2)") (class "Default")
      (node (ref "SG1") (pin "-") (pinfunction "2_-") (pintype "passive"))
      (node (ref "T16") (pin "C") (pinfunction "C_C") (pintype "passive"))
    )
    (net (code "107") (name "Net-(T15A-B)") (class "Default")
      (node (ref "T15") (pin "2") (pinfunction "B_2") (pintype "passive"))
      (node (ref "T15") (pin "4") (pinfunction "E_4") (pintype "passive"))
      (node (ref "U$1") (pin "14") (pinfunction "RTS_14") (pintype "bidirectional"))
    )
    (net (code "108") (name "Net-(T15A-E)") (class "Default")
      (node (ref "T15") (pin "1") (pinfunction "E_1") (pintype "passive"))
      (node (ref "T15") (pin "5") (pinfunction "B_5") (pintype "passive"))
      (node (ref "U$1") (pin "13") (pinfunction "DTR_13") (pintype "bidirectional"))
    )
    (net (code "109") (name "Net-(U$1-D+)") (class "Default")
      (node (ref "R40") (pin "2") (pinfunction "2_2") (pintype "passive"))
      (node (ref "U$1") (pin "5") (pinfunction "D+_5") (pintype "bidirectional"))
    )
    (net (code "110") (name "Net-(U$1-D-)") (class "Default")
      (node (ref "R39") (pin "2") (pinfunction "2_2") (pintype "passive"))
      (node (ref "U$1") (pin "6") (pinfunction "D-_6") (pintype "bidirectional"))
    )
    (net (code "111") (name "Net-(U$2-GPIO32)") (class "Default")
      (node (ref "J1") (pin "2") (pinfunction "2_2") (pintype "passive"))
      (node (ref "R43") (pin "1") (pinfunction "1_1") (pintype "passive"))
      (node (ref "U$2") (pin "P$6") (pinfunction "GPIO32_P$6") (pintype "bidirectional"))
    )
    (net (code "112") (name "Net-(U$2-GPIO33)") (class "Default")
      (node (ref "T16") (pin "B") (pinfunction "B_B") (pintype "passive"))
      (node (ref "U$2") (pin "P$5") (pinfunction "GPIO33_P$5") (pintype "bidirectional"))
    )
    (net (code "113") (name "unconnected-(DIGG-S-PadP$6)") (class "Default")
      (node (ref "DIG") (pin "P$6") (pinfunction "S_P$6") (pintype "passive"))
    )
    (net (code "114") (name "unconnected-(DIGH-S-PadP$7)") (class "Default")
      (node (ref "DIG") (pin "P$7") (pinfunction "S_P$7") (pintype "passive"))
    )
    (net (code "115") (name "unconnected-(IC6-DOUT-Pad2)") (class "Default")
      (node (ref "IC6") (pin "2") (pinfunction "DOUT_2") (pintype "output"))
    )
    (net (code "116") (name "unconnected-(IC6-OUT3-Pad23)") (class "Default")
      (node (ref "IC6") (pin "23") (pinfunction "OUT3_23") (pintype "output"))
    )
    (net (code "117") (name "unconnected-(IC6-OUT4-Pad22)") (class "Default")
      (node (ref "IC6") (pin "22") (pinfunction "OUT4_22") (pintype "output"))
    )
    (net (code "118") (name "unconnected-(IC6-OUT5-Pad21)") (class "Default")
      (node (ref "IC6") (pin "21") (pinfunction "OUT5_21") (pintype "output"))
    )
    (net (code "119") (name "unconnected-(IC6-OUT6-Pad20)") (class "Default")
      (node (ref "IC6") (pin "20") (pinfunction "OUT6_20") (pintype "output"))
    )
    (net (code "120") (name "unconnected-(LED6-DO-Pad2-DOUT)") (class "Default")
      (node (ref "LED6") (pin "2-DOUT") (pinfunction "DO_2-DOUT") (pintype "output"))
    )
    (net (code "121") (name "unconnected-(MP1-NC1-PadP1)") (class "Default")
      (node (ref "MP1") (pin "P1") (pinfunction "NC1_P1") (pintype "bidirectional"))
    )
    (net (code "122") (name "unconnected-(MP1-NC2-PadP8)") (class "Default")
      (node (ref "MP1") (pin "P8") (pinfunction "NC2_P8") (pintype "bidirectional"))
    )
    (net (code "123") (name "unconnected-(MP10-NC1-PadP1)") (class "Default")
      (node (ref "MP10") (pin "P1") (pinfunction "NC1_P1") (pintype "bidirectional"))
    )
    (net (code "124") (name "unconnected-(MP10-NC2-PadP8)") (class "Default")
      (node (ref "MP10") (pin "P8") (pinfunction "NC2_P8") (pintype "bidirectional"))
    )
    (net (code "125") (name "unconnected-(O1-NC1-PadP1)") (class "Default")
      (node (ref "O1") (pin "P1") (pinfunction "NC1_P1") (pintype "bidirectional"))
    )
    (net (code "126") (name "unconnected-(O1-NC2-PadP8)") (class "Default")
      (node (ref "O1") (pin "P8") (pinfunction "NC2_P8") (pintype "bidirectional"))
    )
    (net (code "127") (name "unconnected-(O10-NC1-PadP1)") (class "Default")
      (node (ref "O10") (pin "P1") (pinfunction "NC1_P1") (pintype "bidirectional"))
    )
    (net (code "128") (name "unconnected-(O10-NC2-PadP8)") (class "Default")
      (node (ref "O10") (pin "P8") (pinfunction "NC2_P8") (pintype "bidirectional"))
    )
    (net (code "129") (name "unconnected-(P1-NC1-PadP1)") (class "Default")
      (node (ref "P1") (pin "P1") (pinfunction "NC1_P1") (pintype "bidirectional"))
    )
    (net (code "130") (name "unconnected-(P1-NC2-PadP8)") (class "Default")
      (node (ref "P1") (pin "P8") (pinfunction "NC2_P8") (pintype "bidirectional"))
    )
    (net (code "131") (name "unconnected-(P10-NC1-PadP1)") (class "Default")
      (node (ref "P10") (pin "P1") (pinfunction "NC1_P1") (pintype "bidirectional"))
    )
    (net (code "132") (name "unconnected-(P10-NC2-PadP8)") (class "Default")
      (node (ref "P10") (pin "P8") (pinfunction "NC2_P8") (pintype "bidirectional"))
    )
    (net (code "133") (name "unconnected-(U$1-CTS-Pad9)") (class "Default")
      (node (ref "U$1") (pin "9") (pinfunction "CTS_9") (pintype "bidirectional"))
    )
    (net (code "134") (name "unconnected-(U$1-DCD-Pad12)") (class "Default")
      (node (ref "U$1") (pin "12") (pinfunction "DCD_12") (pintype "bidirectional"))
    )
    (net (code "135") (name "unconnected-(U$1-DSR-Pad10)") (class "Default")
      (node (ref "U$1") (pin "10") (pinfunction "DSR_10") (pintype "bidirectional"))
    )
    (net (code "136") (name "unconnected-(U$1-RI-Pad11)") (class "Default")
      (node (ref "U$1") (pin "11") (pinfunction "RI_11") (pintype "bidirectional"))
    )
    (net (code "137") (name "unconnected-(U$1-RS232-Pad15)") (class "Default")
      (node (ref "U$1") (pin "15") (pinfunction "RS232_15") (pintype "bidirectional"))
    )
    (net (code "138") (name "unconnected-(U$1-RX-Pad3)") (class "Default")
      (node (ref "U$1") (pin "3") (pinfunction "RX_3") (pintype "bidirectional"))
    )
    (net (code "139") (name "unconnected-(U$1-TX-Pad2)") (class "Default")
      (node (ref "U$1") (pin "2") (pinfunction "TX_2") (pintype "bidirectional"))
    )
    (net (code "140") (name "unconnected-(U$1-V3-Pad4)") (class "Default")
      (node (ref "U$1") (pin "4") (pinfunction "V3_4") (pintype "bidirectional"))
    )
    (net (code "141") (name "unconnected-(U$2-CLK-PadP$15)") (class "Default")
      (node (ref "U$2") (pin "P$15") (pinfunction "CLK_P$15") (pintype "bidirectional"))
    )
    (net (code "142") (name "unconnected-(U$2-CMD-PadP$16)") (class "Default")
      (node (ref "U$2") (pin "P$16") (pinfunction "CMD_P$16") (pintype "bidirectional"))
    )
    (net (code "143") (name "unconnected-(U$2-GPIO34-PadP$4)") (class "Default")
      (node (ref "U$2") (pin "P$4") (pinfunction "GPIO34_P$4") (pintype "bidirectional"))
    )
    (net (code "144") (name "unconnected-(U$2-GPIO35-PadP$3)") (class "Default")
      (node (ref "U$2") (pin "P$3") (pinfunction "GPIO35_P$3") (pintype "bidirectional"))
    )
    (net (code "145") (name "unconnected-(U$2-SD0-PadP$18)") (class "Default")
      (node (ref "U$2") (pin "P$18") (pinfunction "SD0_P$18") (pintype "bidirectional"))
    )
    (net (code "146") (name "unconnected-(U$2-SD1-PadP$17)") (class "Default")
      (node (ref "U$2") (pin "P$17") (pinfunction "SD1_P$17") (pintype "bidirectional"))
    )
    (net (code "147") (name "unconnected-(U$2-SD2-PadP$14)") (class "Default")
      (node (ref "U$2") (pin "P$14") (pinfunction "SD2_P$14") (pintype "bidirectional"))
    )
    (net (code "148") (name "unconnected-(U$2-SD3-PadP$13)") (class "Default")
      (node (ref "U$2") (pin "P$13") (pinfunction "SD3_P$13") (pintype "bidirectional"))
    )
    (net (code "149") (name "unconnected-(X1-Pad4)") (class "Default")
      (node (ref "X1") (pin "4") (pinfunction "4_4") (pintype "passive"))
    )
  )
)
